# VL53L1X_Tiny.net
KiCad netlist of a schematic drawn in EAGLE
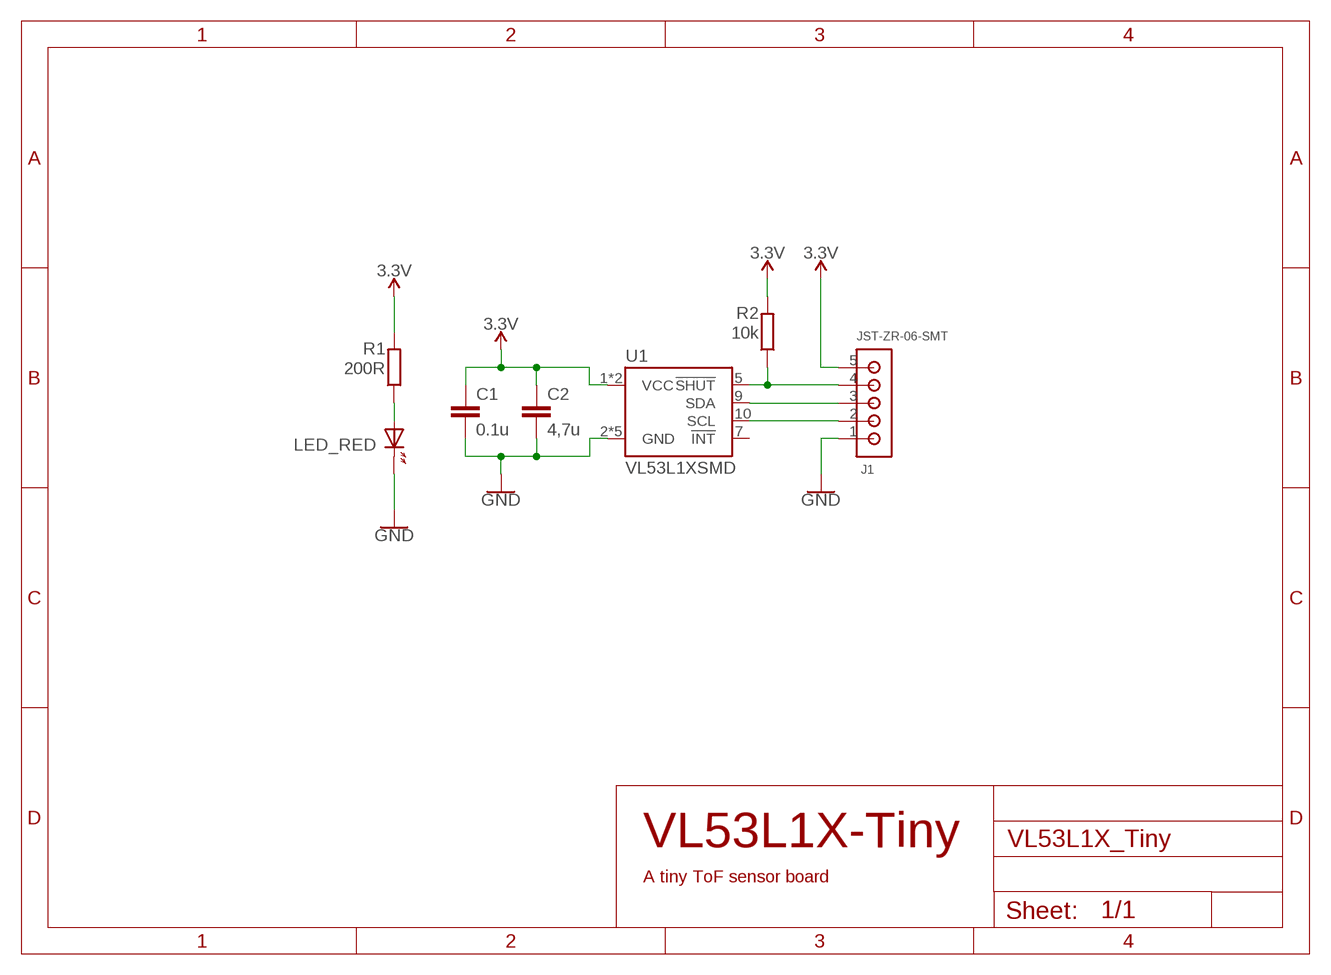
[diagram p0: schematic, sheet 1]

(export (version "E")
  (design (tool "Eeschema 10.0.6"))
  (components
    (comp (ref "C1")
      (value "0.1u")
      (footprint "eagle-import:C0603")
      (libsource (lib "eagle-import") (part "C0603"))
    )
    (comp (ref "C2")
      (value "4,7u")
      (footprint "eagle-import:C0603")
      (libsource (lib "eagle-import") (part "C0603"))
    )
    (comp (ref "J1")
      (value "JST-ZR-06-SMT")
      (footprint "eagle-import:JST_B5B-ZR-SM4-TF_LF_SN_0")
      (fields
        (field (name "DIGIKEY_PART_NUMBER") "455-1684-1-ND")
        (field (name "MF") "JST")
        (field (name "MPN") "B5B-ZR-SM4-TF(LF)(SN)")
      )
      (libsource (lib "eagle-import") (part "JST_B5B-ZR-SM4-TF_LF_SNJST_B5B-ZR-SM4-TF_LF_SN_0_0"))
    )
    (comp (ref "LED_RED")
      (value "CHIP-LED0603")
      (footprint "eagle-import:CHIP-LED0603")
      (libsource (lib "eagle-import") (part "CHIP-LED0603"))
    )
    (comp (ref "R1")
      (value "200R")
      (footprint "eagle-import:R0603")
      (libsource (lib "eagle-import") (part "R0603"))
    )
    (comp (ref "R2")
      (value "10k")
      (footprint "eagle-import:R0603")
      (libsource (lib "eagle-import") (part "R0603"))
    )
    (comp (ref "U1")
      (value "VL53L1XSMD")
      (footprint "eagle-import:VL53L1X")
      (libsource (lib "eagle-import") (part "VL53L1XSMD"))
    )
  )
  (nets
    (net (code "1") (name "3.3V") (class "Default")
      (node (ref "C1") (pin "1") (pinfunction "1_1") (pintype "passive"))
      (node (ref "C2") (pin "1") (pinfunction "1_1") (pintype "passive"))
      (node (ref "J1") (pin "5") (pinfunction "5_5") (pintype "passive"))
      (node (ref "R1") (pin "2") (pinfunction "2_2") (pintype "passive"))
      (node (ref "R2") (pin "2") (pinfunction "2_2") (pintype "passive"))
      (node (ref "U1") (pin "1") (pinfunction "VCC_1") (pintype "bidirectional"))
      (node (ref "U1") (pin "11") (pinfunction "VCC_11") (pintype "bidirectional"))
    )
    (net (code "2") (name "GND") (class "Default")
      (node (ref "C1") (pin "2") (pinfunction "2_2") (pintype "passive"))
      (node (ref "C2") (pin "2") (pinfunction "2_2") (pintype "passive"))
      (node (ref "J1") (pin "1") (pinfunction "1_1") (pintype "passive"))
      (node (ref "LED_RED") (pin "C") (pinfunction "K_C") (pintype "passive"))
      (node (ref "U1") (pin "12") (pinfunction "GND_12") (pintype "bidirectional"))
      (node (ref "U1") (pin "2") (pinfunction "GND_2") (pintype "bidirectional"))
      (node (ref "U1") (pin "3") (pinfunction "GND_3") (pintype "bidirectional"))
      (node (ref "U1") (pin "4") (pinfunction "GND_4") (pintype "bidirectional"))
      (node (ref "U1") (pin "6") (pinfunction "GND_6") (pintype "bidirectional"))
    )
    (net (code "3") (name "Net-(LED_RED-PadA)") (class "Default")
      (node (ref "LED_RED") (pin "A") (pinfunction "A_A") (pintype "passive"))
      (node (ref "R1") (pin "1") (pinfunction "1_1") (pintype "passive"))
    )
    (net (code "4") (name "Net-(U1-SCL)") (class "Default")
      (node (ref "J1") (pin "2") (pinfunction "2_2") (pintype "passive"))
      (node (ref "U1") (pin "10") (pinfunction "SCL_10") (pintype "bidirectional"))
    )
    (net (code "5") (name "Net-(U1-SDA)") (class "Default")
      (node (ref "J1") (pin "3") (pinfunction "3_3") (pintype "passive"))
      (node (ref "U1") (pin "9") (pinfunction "SDA_9") (pintype "bidirectional"))
    )
    (net (code "6") (name "Net-(U1-~{SHUT})") (class "Default")
      (node (ref "J1") (pin "4") (pinfunction "4_4") (pintype "passive"))
      (node (ref "R2") (pin "1") (pinfunction "1_1") (pintype "passive"))
      (node (ref "U1") (pin "5") (pinfunction "~{SHUT}_5") (pintype "bidirectional"))
    )
    (net (code "7") (name "unconnected-(U1-~{INT}-Pad7)") (class "Default")
      (node (ref "U1") (pin "7") (pinfunction "~{INT}_7") (pintype "bidirectional"))
    )
  )
)
